# av_amp_02.net
KiCad netlist of a schematic drawn in EAGLE
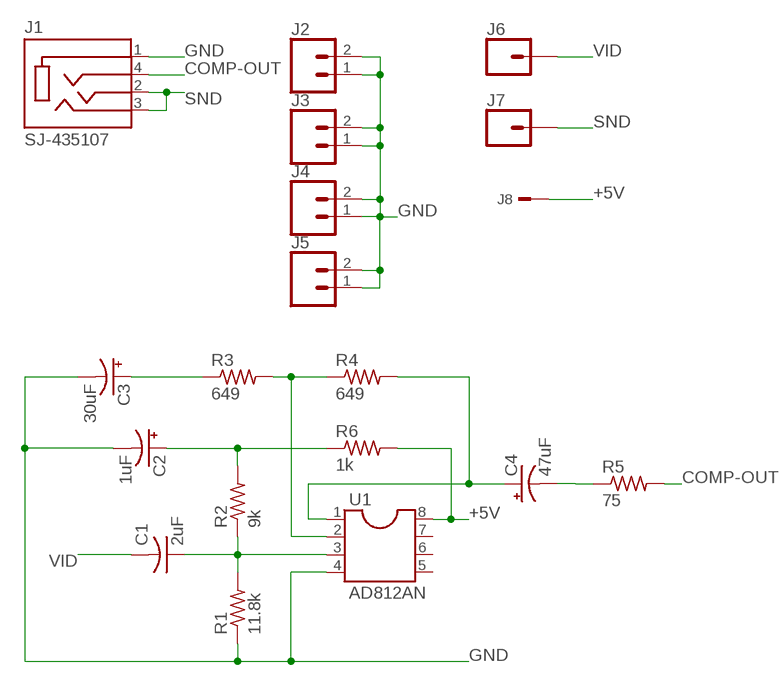
[diagram p0: schematic, sheet 1]

(export (version "E")
  (design (tool "Eeschema 10.0.6"))
  (components
    (comp (ref "C1")
      (value "2uF")
      (footprint "eagle-import:C225-087X268")
      (libsource (lib "eagle-import") (part "C-US225-087X268"))
    )
    (comp (ref "C2")
      (value "1uF")
      (footprint "eagle-import:E5-5")
      (libsource (lib "eagle-import") (part "CPOL-USE5-5"))
    )
    (comp (ref "C3")
      (value "30uF")
      (footprint "eagle-import:E5-10,5")
      (libsource (lib "eagle-import") (part "CPOL-USE5-10.5"))
    )
    (comp (ref "C4")
      (value "47uF")
      (footprint "eagle-import:E5-6")
      (libsource (lib "eagle-import") (part "CPOL-USE5-6"))
    )
    (comp (ref "J1")
      (value "SJ-435107")
      (footprint "eagle-import:CUI_SJ-435107")
      (fields (field (name "MF") "CUI"))
      (libsource (lib "eagle-import") (part "SJ-435107"))
    )
    (comp (ref "J2")
      (value "CONN_02")
      (footprint "eagle-import:1X02")
      (libsource (lib "eagle-import") (part "CONN_02"))
    )
    (comp (ref "J3")
      (value "CONN_02")
      (footprint "eagle-import:1X02")
      (libsource (lib "eagle-import") (part "CONN_02"))
    )
    (comp (ref "J4")
      (value "CONN_02")
      (footprint "eagle-import:1X02")
      (libsource (lib "eagle-import") (part "CONN_02"))
    )
    (comp (ref "J5")
      (value "CONN_02")
      (footprint "eagle-import:1X02")
      (libsource (lib "eagle-import") (part "CONN_02"))
    )
    (comp (ref "J6")
      (value "CONN_01")
      (footprint "eagle-import:1X01")
      (libsource (lib "eagle-import") (part "CONN_01"))
    )
    (comp (ref "J7")
      (value "CONN_01")
      (footprint "eagle-import:1X01")
      (libsource (lib "eagle-import") (part "CONN_01"))
    )
    (comp (ref "J8")
      (value "TSW-101-08-G-S-S-RA")
      (footprint "eagle-import:TSW-101-08-G-S-RA")
      (fields (field (name "MF") "Samtec Inc.") (field (name "MPN") "TSW-101-08-G-S-RA"))
      (libsource (lib "eagle-import") (part "TSW-101--G-S-S-RA08"))
    )
    (comp (ref "R1")
      (value "11.8k")
      (footprint "eagle-import:0207_10")
      (libsource (lib "eagle-import") (part "R-US_0207/10"))
    )
    (comp (ref "R2")
      (value "9k")
      (footprint "eagle-import:0207_10")
      (libsource (lib "eagle-import") (part "R-US_0207/10"))
    )
    (comp (ref "R3")
      (value "649")
      (footprint "eagle-import:0207_10")
      (libsource (lib "eagle-import") (part "R-US_0207/10"))
    )
    (comp (ref "R4")
      (value "649")
      (footprint "eagle-import:0207_10")
      (libsource (lib "eagle-import") (part "R-US_0207/10"))
    )
    (comp (ref "R5")
      (value "75")
      (footprint "eagle-import:0207_10")
      (libsource (lib "eagle-import") (part "R-US_0207/10"))
    )
    (comp (ref "R6")
      (value "1k")
      (footprint "eagle-import:0207_10")
      (libsource (lib "eagle-import") (part "R-US_0207/10"))
    )
    (comp (ref "U1")
      (value "AD812AN")
      (footprint "eagle-import:DIL08")
      (libsource (lib "eagle-import") (part "DIL8"))
    )
  )
  (nets
    (net (code "1") (name "/+5V") (class "Default")
      (node (ref "J8") (pin "1") (pinfunction "1_1") (pintype "passive"))
      (node (ref "R6") (pin "2") (pinfunction "2_2") (pintype "passive"))
      (node (ref "U1") (pin "8") (pinfunction "8_8") (pintype "passive"))
    )
    (net (code "2") (name "/COMP-OUT") (class "Default")
      (node (ref "J1") (pin "4") (pinfunction "RING2_4") (pintype "passive"))
      (node (ref "R5") (pin "2") (pinfunction "2_2") (pintype "passive"))
    )
    (net (code "3") (name "/GND") (class "Default")
      (node (ref "C2") (pin "-") (pinfunction "-_-") (pintype "passive"))
      (node (ref "C3") (pin "-") (pinfunction "-_-") (pintype "passive"))
      (node (ref "J1") (pin "1") (pinfunction "SLEEVE_1") (pintype "passive"))
      (node (ref "J2") (pin "1") (pinfunction "1_1") (pintype "passive"))
      (node (ref "J2") (pin "2") (pinfunction "2_2") (pintype "passive"))
      (node (ref "J3") (pin "1") (pinfunction "1_1") (pintype "passive"))
      (node (ref "J3") (pin "2") (pinfunction "2_2") (pintype "passive"))
      (node (ref "J4") (pin "1") (pinfunction "1_1") (pintype "passive"))
      (node (ref "J4") (pin "2") (pinfunction "2_2") (pintype "passive"))
      (node (ref "J5") (pin "1") (pinfunction "1_1") (pintype "passive"))
      (node (ref "J5") (pin "2") (pinfunction "2_2") (pintype "passive"))
      (node (ref "R1") (pin "1") (pinfunction "1_1") (pintype "passive"))
      (node (ref "U1") (pin "4") (pinfunction "4_4") (pintype "passive"))
    )
    (net (code "4") (name "/SND") (class "Default")
      (node (ref "J1") (pin "2") (pinfunction "TIP_2") (pintype "passive"))
      (node (ref "J1") (pin "3") (pinfunction "RING1_3") (pintype "passive"))
      (node (ref "J7") (pin "1") (pinfunction "1_1") (pintype "passive"))
    )
    (net (code "5") (name "/VID") (class "Default")
      (node (ref "C1") (pin "2") (pinfunction "2_2") (pintype "passive"))
      (node (ref "J6") (pin "1") (pinfunction "1_1") (pintype "passive"))
    )
    (net (code "6") (name "Net-(C1-Pad1)") (class "Default")
      (node (ref "C1") (pin "1") (pinfunction "1_1") (pintype "passive"))
      (node (ref "R1") (pin "2") (pinfunction "2_2") (pintype "passive"))
      (node (ref "R2") (pin "1") (pinfunction "1_1") (pintype "passive"))
      (node (ref "U1") (pin "3") (pinfunction "3_3") (pintype "passive"))
    )
    (net (code "7") (name "Net-(C2-Pad+)") (class "Default")
      (node (ref "C2") (pin "+") (pinfunction "+_+") (pintype "passive"))
      (node (ref "R2") (pin "2") (pinfunction "2_2") (pintype "passive"))
      (node (ref "R6") (pin "1") (pinfunction "1_1") (pintype "passive"))
    )
    (net (code "8") (name "Net-(C3-Pad+)") (class "Default")
      (node (ref "C3") (pin "+") (pinfunction "+_+") (pintype "passive"))
      (node (ref "R3") (pin "1") (pinfunction "1_1") (pintype "passive"))
    )
    (net (code "9") (name "Net-(C4-Pad+)") (class "Default")
      (node (ref "C4") (pin "+") (pinfunction "+_+") (pintype "passive"))
      (node (ref "R4") (pin "2") (pinfunction "2_2") (pintype "passive"))
      (node (ref "U1") (pin "1") (pinfunction "1_1") (pintype "passive"))
    )
    (net (code "10") (name "Net-(C4-Pad-)") (class "Default")
      (node (ref "C4") (pin "-") (pinfunction "-_-") (pintype "passive"))
      (node (ref "R5") (pin "1") (pinfunction "1_1") (pintype "passive"))
    )
    (net (code "11") (name "Net-(R3-Pad2)") (class "Default")
      (node (ref "R3") (pin "2") (pinfunction "2_2") (pintype "passive"))
      (node (ref "R4") (pin "1") (pinfunction "1_1") (pintype "passive"))
      (node (ref "U1") (pin "2") (pinfunction "2_2") (pintype "passive"))
    )
    (net (code "12") (name "unconnected-(U1-Pad5)") (class "Default")
      (node (ref "U1") (pin "5") (pinfunction "5_5") (pintype "passive"))
    )
    (net (code "13") (name "unconnected-(U1-Pad6)") (class "Default")
      (node (ref "U1") (pin "6") (pinfunction "6_6") (pintype "passive"))
    )
    (net (code "14") (name "unconnected-(U1-Pad7)") (class "Default")
      (node (ref "U1") (pin "7") (pinfunction "7_7") (pintype "passive"))
    )
  )
)
